# A05_ENCODER_NTC.net
KiCad netlist of a schematic drawn in Altium Designer
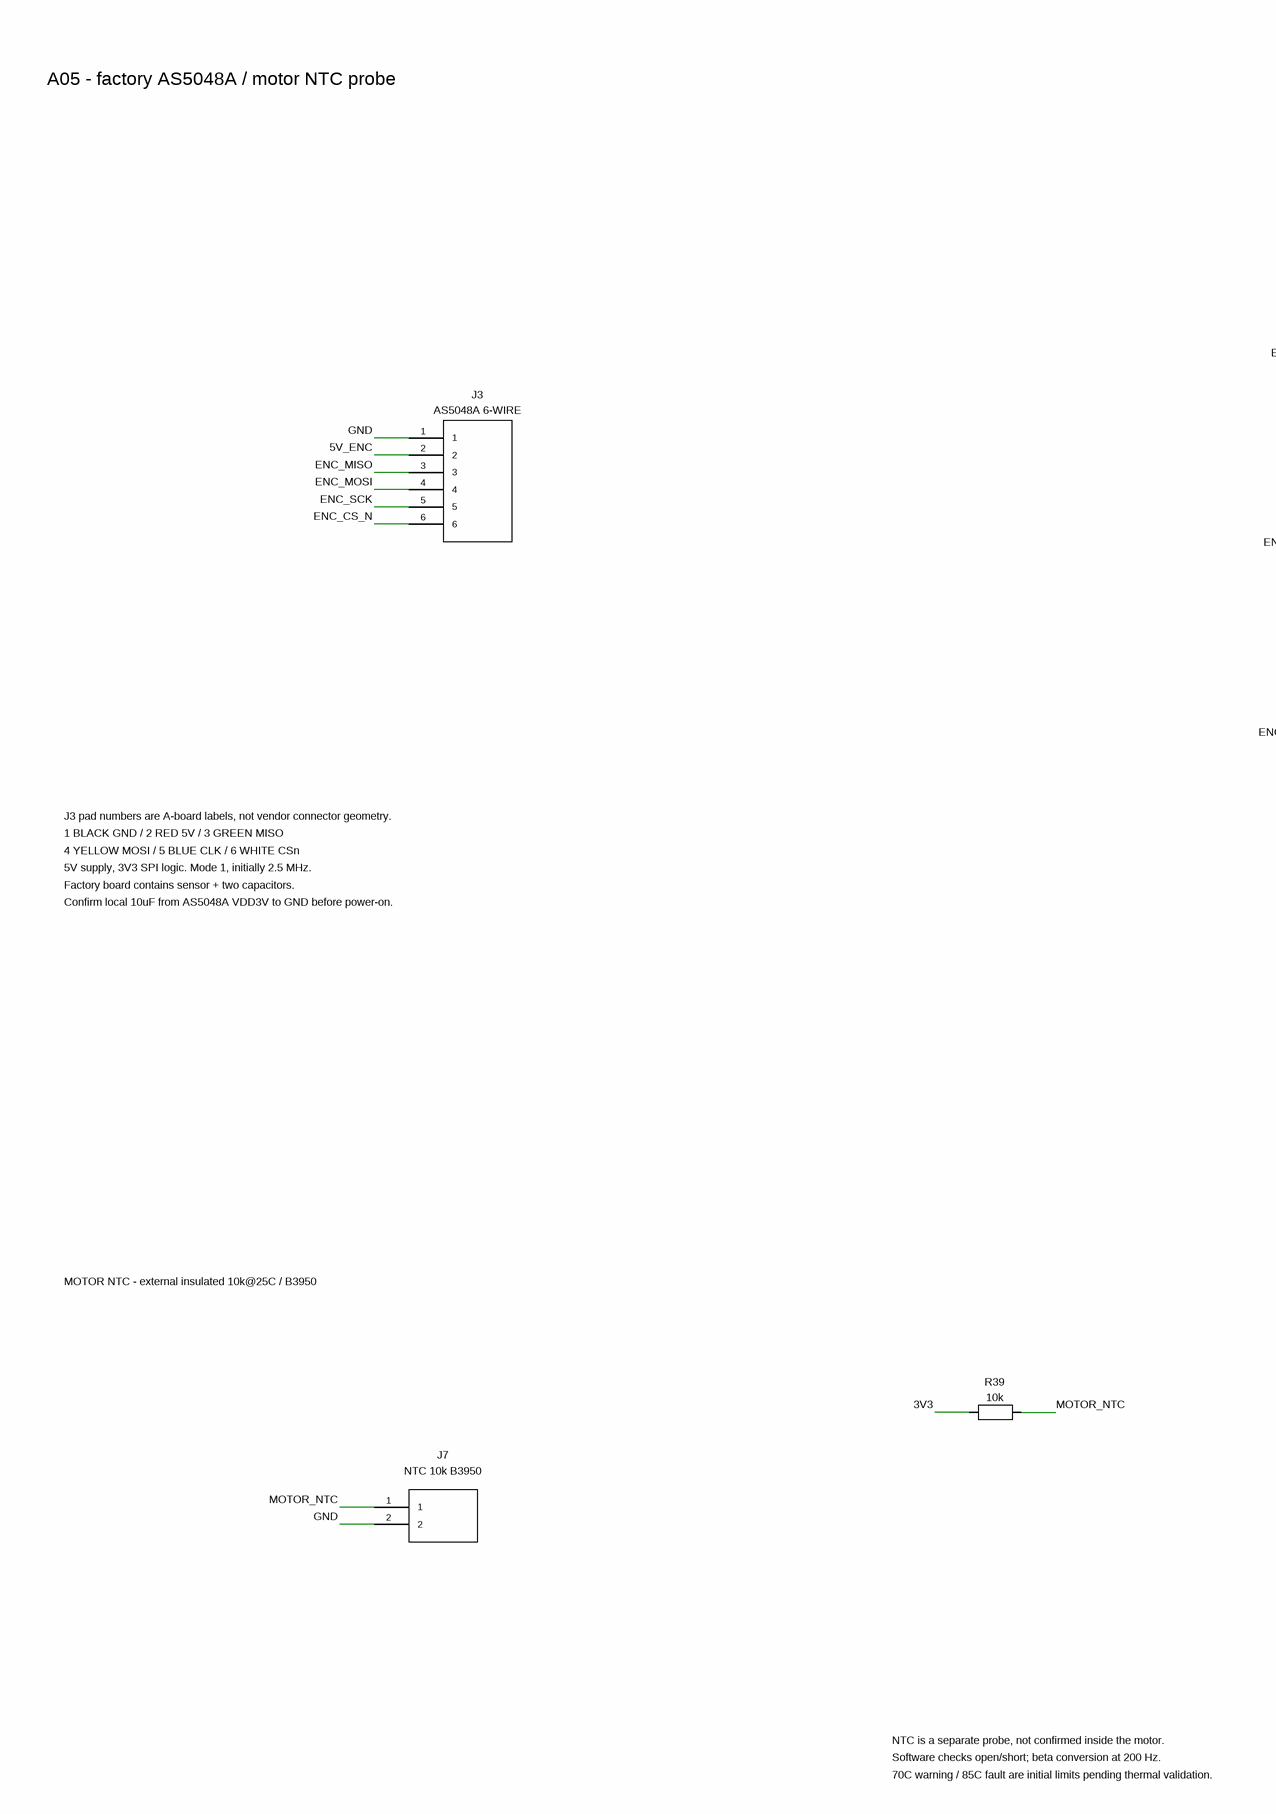
[diagram p0: A05_ENCODER_NTC.SchDoc, left]
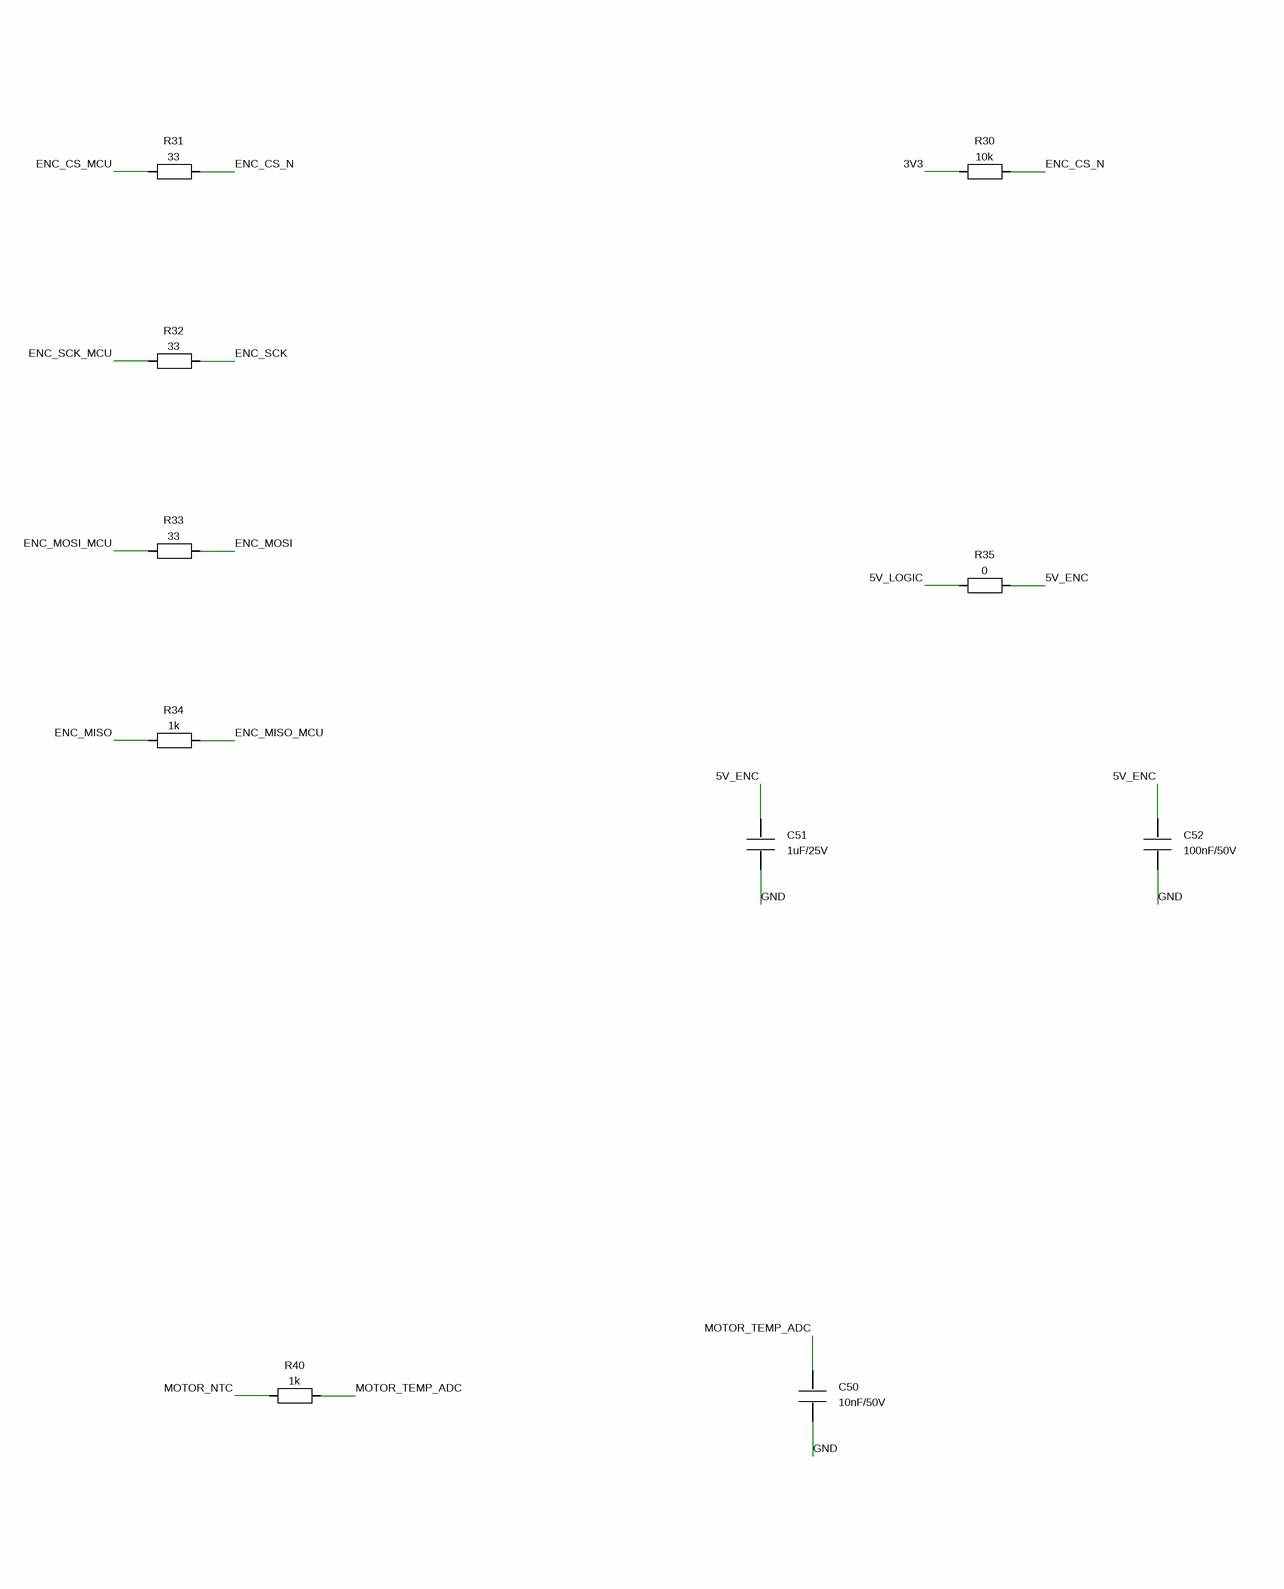
[diagram p1: A05_ENCODER_NTC.SchDoc, right]

(export (version "E")
  (design (tool "Eeschema 10.0.6"))
  (components
    (comp (ref "C50")
      (value "10nF/50V")
      (footprint "User_STM32F407_Ctrl:C0603_M")
      (description "电容")
      (fields (field (name "MPN") "CC0603KRX7R9BB103"))
      (libsource (lib "altium-import") (part "root_0_C_"))
    )
    (comp (ref "C51")
      (value "1uF/25V")
      (footprint "User_STM32F407_Ctrl:C0603_M")
      (description "电容")
      (fields (field (name "MPN") "CL10A105KA8NNNC"))
      (libsource (lib "altium-import") (part "root_0_C_"))
    )
    (comp (ref "C52")
      (value "100nF/50V")
      (footprint "User_STM32F407_Ctrl:C0603_M")
      (description "电容")
      (fields (field (name "MPN") "CL10B104KB8NNNC"))
      (libsource (lib "altium-import") (part "root_0_C_"))
    )
    (comp (ref "J3")
      (value "AS5048A 6-WIRE")
      (description "AS5048A编码器焊线口")
      (fields (field (name "MPN") "6标号焊盘；不假定原厂插头脚号"))
      (libsource (lib "altium-import") (part "root_0_Connector_6_"))
    )
    (comp (ref "J7")
      (value "NTC 10k B3950")
      (footprint "GL30_Adjusted_User:GL30_B2B_PH_K_S_FR4_D085")
      (description "电机温度探头")
      (fields (field (name "MPN") "JST B2B-PH-K-S(LF)(SN)"))
      (libsource (lib "altium-import") (part "root_0_Connector_2_"))
    )
    (comp (ref "R30")
      (value "10k")
      (footprint "User_STM32F407_Ctrl:R0603_M")
      (description "电阻")
      (fields (field (name "MPN") "通用厚膜 10k 1% 0.1 W"))
      (libsource (lib "altium-import") (part "root_1_R_"))
    )
    (comp (ref "R31")
      (value "33")
      (footprint "User_STM32F407_Ctrl:R0603_M")
      (description "电阻")
      (fields (field (name "MPN") "通用厚膜 33 1% 0.1 W"))
      (libsource (lib "altium-import") (part "root_1_R_"))
    )
    (comp (ref "R32")
      (value "33")
      (footprint "User_STM32F407_Ctrl:R0603_M")
      (description "电阻")
      (fields (field (name "MPN") "通用厚膜 33 1% 0.1 W"))
      (libsource (lib "altium-import") (part "root_1_R_"))
    )
    (comp (ref "R33")
      (value "33")
      (footprint "User_STM32F407_Ctrl:R0603_M")
      (description "电阻")
      (fields (field (name "MPN") "通用厚膜 33 1% 0.1 W"))
      (libsource (lib "altium-import") (part "root_1_R_"))
    )
    (comp (ref "R34")
      (value "1k")
      (footprint "User_STM32F407_Ctrl:R0603_M")
      (description "电阻")
      (fields (field (name "MPN") "通用厚膜 1k 1% 0.1 W"))
      (libsource (lib "altium-import") (part "root_1_R_"))
    )
    (comp (ref "R35")
      (value "0")
      (footprint "User_STM32F407_Ctrl:R0603_M")
      (description "电阻")
      (fields (field (name "MPN") "通用0Ω跳线 0.1 W"))
      (libsource (lib "altium-import") (part "root_1_R_"))
    )
    (comp (ref "R39")
      (value "10k")
      (footprint "User_STM32F407_Ctrl:R0603_M")
      (description "电阻")
      (fields (field (name "MPN") "通用厚膜 10k 1% 0.1 W"))
      (libsource (lib "altium-import") (part "root_1_R_"))
    )
    (comp (ref "R40")
      (value "1k")
      (footprint "User_STM32F407_Ctrl:R0603_M")
      (description "电阻")
      (fields (field (name "MPN") "通用厚膜 1k 1% 0.1 W"))
      (libsource (lib "altium-import") (part "root_1_R_"))
    )
  )
  (nets
    (net (code "1") (name "/3V3") (class "Default")
      (node (ref "R30") (pin "1") (pintype "passive"))
      (node (ref "R39") (pin "1") (pintype "passive"))
    )
    (net (code "2") (name "/5V_ENC") (class "Default")
      (node (ref "C51") (pin "1") (pintype "passive"))
      (node (ref "C52") (pin "1") (pintype "passive"))
      (node (ref "J3") (pin "2") (pinfunction "2_2") (pintype "passive"))
      (node (ref "R35") (pin "2") (pintype "passive"))
    )
    (net (code "3") (name "/5V_LOGIC") (class "Default") (node (ref "R35") (pin "1") (pintype "passive")))
    (net (code "4") (name "/ENC_CS_MCU") (class "Default") (node (ref "R31") (pin "1") (pintype "passive")))
    (net (code "5") (name "/ENC_CS_N") (class "Default")
      (node (ref "J3") (pin "6") (pinfunction "6_6") (pintype "passive"))
      (node (ref "R30") (pin "2") (pintype "passive"))
      (node (ref "R31") (pin "2") (pintype "passive"))
    )
    (net (code "6") (name "/ENC_MISO") (class "Default")
      (node (ref "J3") (pin "3") (pinfunction "3_3") (pintype "passive"))
      (node (ref "R34") (pin "1") (pintype "passive"))
    )
    (net (code "7") (name "/ENC_MISO_MCU") (class "Default") (node (ref "R34") (pin "2") (pintype "passive")))
    (net (code "8") (name "/ENC_MOSI") (class "Default")
      (node (ref "J3") (pin "4") (pinfunction "4_4") (pintype "passive"))
      (node (ref "R33") (pin "2") (pintype "passive"))
    )
    (net (code "9") (name "/ENC_MOSI_MCU") (class "Default") (node (ref "R33") (pin "1") (pintype "passive")))
    (net (code "10") (name "/ENC_SCK") (class "Default")
      (node (ref "J3") (pin "5") (pinfunction "5_5") (pintype "passive"))
      (node (ref "R32") (pin "2") (pintype "passive"))
    )
    (net (code "11") (name "/ENC_SCK_MCU") (class "Default") (node (ref "R32") (pin "1") (pintype "passive")))
    (net (code "12") (name "/GND") (class "Default")
      (node (ref "C50") (pin "2") (pintype "passive"))
      (node (ref "C51") (pin "2") (pintype "passive"))
      (node (ref "C52") (pin "2") (pintype "passive"))
      (node (ref "J3") (pin "1") (pinfunction "1_1") (pintype "passive"))
      (node (ref "J7") (pin "2") (pinfunction "2_2") (pintype "passive"))
    )
    (net (code "13") (name "/MOTOR_NTC") (class "Default")
      (node (ref "J7") (pin "1") (pinfunction "1_1") (pintype "passive"))
      (node (ref "R39") (pin "2") (pintype "passive"))
      (node (ref "R40") (pin "1") (pintype "passive"))
    )
    (net (code "14") (name "/MOTOR_TEMP_ADC") (class "Default")
      (node (ref "C50") (pin "1") (pintype "passive"))
      (node (ref "R40") (pin "2") (pintype "passive"))
    )
  )
)
